# Pour_Over_Board_Internal_Pullup.net
KiCad netlist of a schematic drawn in EAGLE
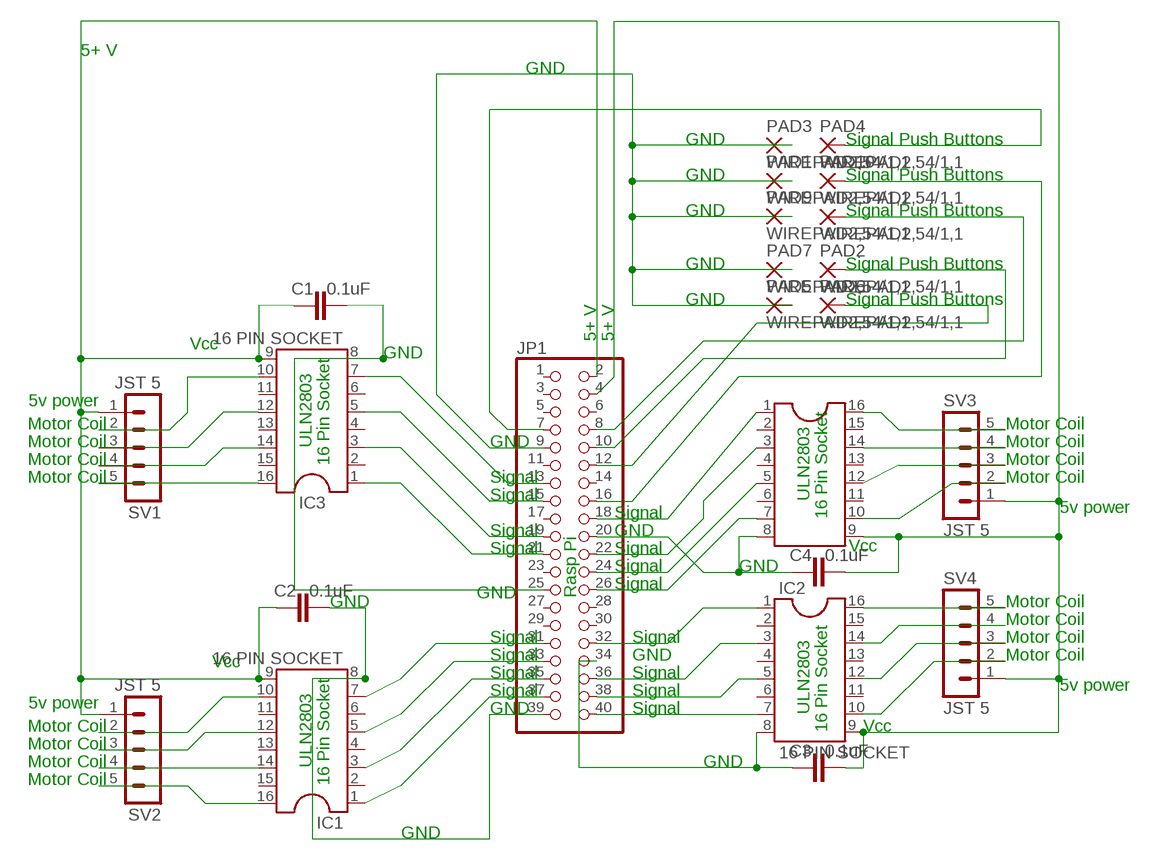
[diagram p0: schematic, sheet 1]

(export (version "E")
  (design (tool "Eeschema 10.0.6"))
  (components
    (comp (ref "C1")
      (value "0.1uF")
      (footprint "eagle-import:CAP-PTH-SMALL-KIT")
      (libsource (lib "eagle-import") (part "0.1UF-KIT-EZ-50V-20%"))
    )
    (comp (ref "C2")
      (value "0.1uF")
      (footprint "eagle-import:CAP-PTH-SMALL-KIT")
      (libsource (lib "eagle-import") (part "0.1UF-KIT-EZ-50V-20%"))
    )
    (comp (ref "C3")
      (value "0.1uF")
      (footprint "eagle-import:CAP-PTH-SMALL-KIT")
      (libsource (lib "eagle-import") (part "0.1UF-KIT-EZ-50V-20%"))
    )
    (comp (ref "C4")
      (value "0.1uF")
      (footprint "eagle-import:CAP-PTH-SMALL-KIT")
      (libsource (lib "eagle-import") (part "0.1UF-KIT-EZ-50V-20%"))
    )
    (comp (ref "IC1")
      (value "16 PIN SOCKET")
      (footprint "eagle-import:SOCKET-16")
      (libsource (lib "eagle-import") (part "DIL16S"))
    )
    (comp (ref "IC2")
      (value "16 PIN SOCKET")
      (footprint "eagle-import:SOCKET-16")
      (libsource (lib "eagle-import") (part "DIL16S"))
    )
    (comp (ref "IC3")
      (value "16 PIN SOCKET")
      (footprint "eagle-import:SOCKET-16")
      (libsource (lib "eagle-import") (part "DIL16S"))
    )
    (comp (ref "IC4")
      (value "16 PIN SOCKET")
      (footprint "eagle-import:SOCKET-16")
      (libsource (lib "eagle-import") (part "DIL16S"))
    )
    (comp (ref "JP1")
      (value "RaspPiZero")
      (footprint "eagle-import:2X20")
      (libsource (lib "eagle-import") (part "PINHD-2X20"))
    )
    (comp (ref "PAD1")
      (value "WIREPAD2,54/1,1")
      (footprint "eagle-import:2,54_1,1")
      (libsource (lib "eagle-import") (part "WIREPAD2,54/1,1"))
    )
    (comp (ref "PAD2")
      (value "WIREPAD2,54/1,1")
      (footprint "eagle-import:2,54_1,1")
      (libsource (lib "eagle-import") (part "WIREPAD2,54/1,1"))
    )
    (comp (ref "PAD3")
      (value "WIREPAD2,54/1,1")
      (footprint "eagle-import:2,54_1,1")
      (libsource (lib "eagle-import") (part "WIREPAD2,54/1,1"))
    )
    (comp (ref "PAD4")
      (value "WIREPAD2,54/1,1")
      (footprint "eagle-import:2,54_1,1")
      (libsource (lib "eagle-import") (part "WIREPAD2,54/1,1"))
    )
    (comp (ref "PAD5")
      (value "WIREPAD2,54/1,1")
      (footprint "eagle-import:2,54_1,1")
      (libsource (lib "eagle-import") (part "WIREPAD2,54/1,1"))
    )
    (comp (ref "PAD6")
      (value "WIREPAD2,54/1,1")
      (footprint "eagle-import:2,54_1,1")
      (libsource (lib "eagle-import") (part "WIREPAD2,54/1,1"))
    )
    (comp (ref "PAD7")
      (value "WIREPAD2,54/1,1")
      (footprint "eagle-import:2,54_1,1")
      (libsource (lib "eagle-import") (part "WIREPAD2,54/1,1"))
    )
    (comp (ref "PAD8")
      (value "WIREPAD2,54/1,1")
      (footprint "eagle-import:2,54_1,1")
      (libsource (lib "eagle-import") (part "WIREPAD2,54/1,1"))
    )
    (comp (ref "PAD9")
      (value "WIREPAD2,54/1,1")
      (footprint "eagle-import:2,54_1,1")
      (libsource (lib "eagle-import") (part "WIREPAD2,54/1,1"))
    )
    (comp (ref "PAD10")
      (value "WIREPAD2,54/1,1")
      (footprint "eagle-import:2,54_1,1")
      (libsource (lib "eagle-import") (part "WIREPAD2,54/1,1"))
    )
    (comp (ref "SV1")
      (value "JST 5")
      (footprint "eagle-import:MA05-1")
      (libsource (lib "eagle-import") (part "MA05-1"))
    )
    (comp (ref "SV2")
      (value "JST 5")
      (footprint "eagle-import:MA05-1")
      (libsource (lib "eagle-import") (part "MA05-1"))
    )
    (comp (ref "SV3")
      (value "JST 5")
      (footprint "eagle-import:MA05-1")
      (libsource (lib "eagle-import") (part "MA05-1"))
    )
    (comp (ref "SV4")
      (value "JST 5")
      (footprint "eagle-import:MA05-1")
      (libsource (lib "eagle-import") (part "MA05-1"))
    )
  )
  (nets
    (net (code "1") (name "Net-(C1-Pad1)") (class "Default")
      (node (ref "C1") (pin "1") (pinfunction "1_1") (pintype "passive"))
      (node (ref "C2") (pin "1") (pinfunction "1_1") (pintype "passive"))
      (node (ref "IC1") (pin "9") (pinfunction "9_9") (pintype "passive"))
      (node (ref "IC3") (pin "9") (pinfunction "9_9") (pintype "passive"))
      (node (ref "JP1") (pin "2") (pinfunction "2_2") (pintype "passive"))
      (node (ref "SV1") (pin "1") (pinfunction "1_1") (pintype "passive"))
      (node (ref "SV2") (pin "1") (pinfunction "1_1") (pintype "passive"))
    )
    (net (code "2") (name "Net-(C1-Pad2)") (class "Default")
      (node (ref "C1") (pin "2") (pinfunction "2_2") (pintype "passive"))
      (node (ref "IC3") (pin "8") (pinfunction "8_8") (pintype "passive"))
      (node (ref "JP1") (pin "25") (pinfunction "25_25") (pintype "passive"))
    )
    (net (code "3") (name "Net-(C2-Pad2)") (class "Default")
      (node (ref "C2") (pin "2") (pinfunction "2_2") (pintype "passive"))
      (node (ref "IC1") (pin "8") (pinfunction "8_8") (pintype "passive"))
      (node (ref "JP1") (pin "39") (pinfunction "39_39") (pintype "passive"))
    )
    (net (code "4") (name "Net-(C3-Pad1)") (class "Default")
      (node (ref "C3") (pin "1") (pinfunction "1_1") (pintype "passive"))
      (node (ref "IC2") (pin "8") (pinfunction "8_8") (pintype "passive"))
      (node (ref "JP1") (pin "34") (pinfunction "34_34") (pintype "passive"))
    )
    (net (code "5") (name "Net-(C3-Pad2)") (class "Default")
      (node (ref "C3") (pin "2") (pinfunction "2_2") (pintype "passive"))
      (node (ref "C4") (pin "2") (pinfunction "2_2") (pintype "passive"))
      (node (ref "IC2") (pin "9") (pinfunction "9_9") (pintype "passive"))
      (node (ref "IC4") (pin "9") (pinfunction "9_9") (pintype "passive"))
      (node (ref "JP1") (pin "4") (pinfunction "4_4") (pintype "passive"))
      (node (ref "SV3") (pin "1") (pinfunction "1_1") (pintype "passive"))
      (node (ref "SV4") (pin "1") (pinfunction "1_1") (pintype "passive"))
    )
    (net (code "6") (name "Net-(C4-Pad1)") (class "Default")
      (node (ref "C4") (pin "1") (pinfunction "1_1") (pintype "passive"))
      (node (ref "IC4") (pin "8") (pinfunction "8_8") (pintype "passive"))
      (node (ref "JP1") (pin "20") (pinfunction "20_20") (pintype "passive"))
    )
    (net (code "7") (name "Net-(IC1-Pad1)") (class "Default")
      (node (ref "IC1") (pin "1") (pinfunction "1_1") (pintype "passive"))
      (node (ref "JP1") (pin "37") (pinfunction "37_37") (pintype "passive"))
    )
    (net (code "8") (name "Net-(IC1-Pad3)") (class "Default")
      (node (ref "IC1") (pin "3") (pinfunction "3_3") (pintype "passive"))
      (node (ref "JP1") (pin "35") (pinfunction "35_35") (pintype "passive"))
    )
    (net (code "9") (name "Net-(IC1-Pad5)") (class "Default")
      (node (ref "IC1") (pin "5") (pinfunction "5_5") (pintype "passive"))
      (node (ref "JP1") (pin "33") (pinfunction "33_33") (pintype "passive"))
    )
    (net (code "10") (name "Net-(IC1-Pad7)") (class "Default")
      (node (ref "IC1") (pin "7") (pinfunction "7_7") (pintype "passive"))
      (node (ref "JP1") (pin "31") (pinfunction "31_31") (pintype "passive"))
    )
    (net (code "11") (name "Net-(IC1-Pad10)") (class "Default")
      (node (ref "IC1") (pin "10") (pinfunction "10_10") (pintype "passive"))
      (node (ref "SV2") (pin "2") (pinfunction "2_2") (pintype "passive"))
    )
    (net (code "12") (name "Net-(IC1-Pad12)") (class "Default")
      (node (ref "IC1") (pin "12") (pinfunction "12_12") (pintype "passive"))
      (node (ref "SV2") (pin "3") (pinfunction "3_3") (pintype "passive"))
    )
    (net (code "13") (name "Net-(IC1-Pad14)") (class "Default")
      (node (ref "IC1") (pin "14") (pinfunction "14_14") (pintype "passive"))
      (node (ref "SV2") (pin "4") (pinfunction "4_4") (pintype "passive"))
    )
    (net (code "14") (name "Net-(IC1-Pad16)") (class "Default")
      (node (ref "IC1") (pin "16") (pinfunction "16_16") (pintype "passive"))
      (node (ref "SV2") (pin "5") (pinfunction "5_5") (pintype "passive"))
    )
    (net (code "15") (name "Net-(IC2-Pad1)") (class "Default")
      (node (ref "IC2") (pin "1") (pinfunction "1_1") (pintype "passive"))
      (node (ref "JP1") (pin "32") (pinfunction "32_32") (pintype "passive"))
    )
    (net (code "16") (name "Net-(IC2-Pad3)") (class "Default")
      (node (ref "IC2") (pin "3") (pinfunction "3_3") (pintype "passive"))
      (node (ref "JP1") (pin "36") (pinfunction "36_36") (pintype "passive"))
    )
    (net (code "17") (name "Net-(IC2-Pad5)") (class "Default")
      (node (ref "IC2") (pin "5") (pinfunction "5_5") (pintype "passive"))
      (node (ref "JP1") (pin "38") (pinfunction "38_38") (pintype "passive"))
    )
    (net (code "18") (name "Net-(IC2-Pad7)") (class "Default")
      (node (ref "IC2") (pin "7") (pinfunction "7_7") (pintype "passive"))
      (node (ref "JP1") (pin "40") (pinfunction "40_40") (pintype "passive"))
    )
    (net (code "19") (name "Net-(IC2-Pad10)") (class "Default")
      (node (ref "IC2") (pin "10") (pinfunction "10_10") (pintype "passive"))
      (node (ref "SV4") (pin "2") (pinfunction "2_2") (pintype "passive"))
    )
    (net (code "20") (name "Net-(IC2-Pad12)") (class "Default")
      (node (ref "IC2") (pin "12") (pinfunction "12_12") (pintype "passive"))
      (node (ref "SV4") (pin "3") (pinfunction "3_3") (pintype "passive"))
    )
    (net (code "21") (name "Net-(IC2-Pad14)") (class "Default")
      (node (ref "IC2") (pin "14") (pinfunction "14_14") (pintype "passive"))
      (node (ref "SV4") (pin "4") (pinfunction "4_4") (pintype "passive"))
    )
    (net (code "22") (name "Net-(IC2-Pad16)") (class "Default")
      (node (ref "IC2") (pin "16") (pinfunction "16_16") (pintype "passive"))
      (node (ref "SV4") (pin "5") (pinfunction "5_5") (pintype "passive"))
    )
    (net (code "23") (name "Net-(IC3-Pad1)") (class "Default")
      (node (ref "IC3") (pin "1") (pinfunction "1_1") (pintype "passive"))
      (node (ref "JP1") (pin "21") (pinfunction "21_21") (pintype "passive"))
    )
    (net (code "24") (name "Net-(IC3-Pad3)") (class "Default")
      (node (ref "IC3") (pin "3") (pinfunction "3_3") (pintype "passive"))
      (node (ref "JP1") (pin "19") (pinfunction "19_19") (pintype "passive"))
    )
    (net (code "25") (name "Net-(IC3-Pad5)") (class "Default")
      (node (ref "IC3") (pin "5") (pinfunction "5_5") (pintype "passive"))
      (node (ref "JP1") (pin "15") (pinfunction "15_15") (pintype "passive"))
    )
    (net (code "26") (name "Net-(IC3-Pad7)") (class "Default")
      (node (ref "IC3") (pin "7") (pinfunction "7_7") (pintype "passive"))
      (node (ref "JP1") (pin "13") (pinfunction "13_13") (pintype "passive"))
    )
    (net (code "27") (name "Net-(IC3-Pad10)") (class "Default")
      (node (ref "IC3") (pin "10") (pinfunction "10_10") (pintype "passive"))
      (node (ref "SV1") (pin "2") (pinfunction "2_2") (pintype "passive"))
    )
    (net (code "28") (name "Net-(IC3-Pad12)") (class "Default")
      (node (ref "IC3") (pin "12") (pinfunction "12_12") (pintype "passive"))
      (node (ref "SV1") (pin "3") (pinfunction "3_3") (pintype "passive"))
    )
    (net (code "29") (name "Net-(IC3-Pad14)") (class "Default")
      (node (ref "IC3") (pin "14") (pinfunction "14_14") (pintype "passive"))
      (node (ref "SV1") (pin "4") (pinfunction "4_4") (pintype "passive"))
    )
    (net (code "30") (name "Net-(IC3-Pad16)") (class "Default")
      (node (ref "IC3") (pin "16") (pinfunction "16_16") (pintype "passive"))
      (node (ref "SV1") (pin "5") (pinfunction "5_5") (pintype "passive"))
    )
    (net (code "31") (name "Net-(IC4-Pad1)") (class "Default")
      (node (ref "IC4") (pin "1") (pinfunction "1_1") (pintype "passive"))
      (node (ref "JP1") (pin "18") (pinfunction "18_18") (pintype "passive"))
    )
    (net (code "32") (name "Net-(IC4-Pad3)") (class "Default")
      (node (ref "IC4") (pin "3") (pinfunction "3_3") (pintype "passive"))
      (node (ref "JP1") (pin "22") (pinfunction "22_22") (pintype "passive"))
    )
    (net (code "33") (name "Net-(IC4-Pad5)") (class "Default")
      (node (ref "IC4") (pin "5") (pinfunction "5_5") (pintype "passive"))
      (node (ref "JP1") (pin "24") (pinfunction "24_24") (pintype "passive"))
    )
    (net (code "34") (name "Net-(IC4-Pad7)") (class "Default")
      (node (ref "IC4") (pin "7") (pinfunction "7_7") (pintype "passive"))
      (node (ref "JP1") (pin "26") (pinfunction "26_26") (pintype "passive"))
    )
    (net (code "35") (name "Net-(IC4-Pad10)") (class "Default")
      (node (ref "IC4") (pin "10") (pinfunction "10_10") (pintype "passive"))
      (node (ref "SV3") (pin "2") (pinfunction "2_2") (pintype "passive"))
    )
    (net (code "36") (name "Net-(IC4-Pad12)") (class "Default")
      (node (ref "IC4") (pin "12") (pinfunction "12_12") (pintype "passive"))
      (node (ref "SV3") (pin "3") (pinfunction "3_3") (pintype "passive"))
    )
    (net (code "37") (name "Net-(IC4-Pad14)") (class "Default")
      (node (ref "IC4") (pin "14") (pinfunction "14_14") (pintype "passive"))
      (node (ref "SV3") (pin "4") (pinfunction "4_4") (pintype "passive"))
    )
    (net (code "38") (name "Net-(IC4-Pad16)") (class "Default")
      (node (ref "IC4") (pin "16") (pinfunction "16_16") (pintype "passive"))
      (node (ref "SV3") (pin "5") (pinfunction "5_5") (pintype "passive"))
    )
    (net (code "39") (name "Net-(PAD1-P)") (class "Default")
      (node (ref "JP1") (pin "9") (pinfunction "9_9") (pintype "passive"))
      (node (ref "PAD1") (pin "1") (pinfunction "P_1") (pintype "passive"))
      (node (ref "PAD3") (pin "1") (pinfunction "P_1") (pintype "passive"))
      (node (ref "PAD5") (pin "1") (pinfunction "P_1") (pintype "passive"))
      (node (ref "PAD7") (pin "1") (pinfunction "P_1") (pintype "passive"))
      (node (ref "PAD9") (pin "1") (pinfunction "P_1") (pintype "passive"))
    )
    (net (code "40") (name "Net-(PAD2-P)") (class "Default")
      (node (ref "JP1") (pin "10") (pinfunction "10_10") (pintype "passive"))
      (node (ref "PAD2") (pin "1") (pinfunction "P_1") (pintype "passive"))
    )
    (net (code "41") (name "Net-(PAD4-P)") (class "Default")
      (node (ref "JP1") (pin "7") (pinfunction "7_7") (pintype "passive"))
      (node (ref "PAD4") (pin "1") (pinfunction "P_1") (pintype "passive"))
    )
    (net (code "42") (name "Net-(PAD6-P)") (class "Default")
      (node (ref "JP1") (pin "12") (pinfunction "12_12") (pintype "passive"))
      (node (ref "PAD6") (pin "1") (pinfunction "P_1") (pintype "passive"))
    )
    (net (code "43") (name "Net-(PAD8-P)") (class "Default")
      (node (ref "JP1") (pin "8") (pinfunction "8_8") (pintype "passive"))
      (node (ref "PAD8") (pin "1") (pinfunction "P_1") (pintype "passive"))
    )
    (net (code "44") (name "Net-(PAD10-P)") (class "Default")
      (node (ref "JP1") (pin "16") (pinfunction "16_16") (pintype "passive"))
      (node (ref "PAD10") (pin "1") (pinfunction "P_1") (pintype "passive"))
    )
    (net (code "45") (name "unconnected-(IC1-Pad2)") (class "Default")
      (node (ref "IC1") (pin "2") (pinfunction "2_2") (pintype "passive"))
    )
    (net (code "46") (name "unconnected-(IC1-Pad4)") (class "Default")
      (node (ref "IC1") (pin "4") (pinfunction "4_4") (pintype "passive"))
    )
    (net (code "47") (name "unconnected-(IC1-Pad6)") (class "Default")
      (node (ref "IC1") (pin "6") (pinfunction "6_6") (pintype "passive"))
    )
    (net (code "48") (name "unconnected-(IC1-Pad11)") (class "Default")
      (node (ref "IC1") (pin "11") (pinfunction "11_11") (pintype "passive"))
    )
    (net (code "49") (name "unconnected-(IC1-Pad13)") (class "Default")
      (node (ref "IC1") (pin "13") (pinfunction "13_13") (pintype "passive"))
    )
    (net (code "50") (name "unconnected-(IC1-Pad15)") (class "Default")
      (node (ref "IC1") (pin "15") (pinfunction "15_15") (pintype "passive"))
    )
    (net (code "51") (name "unconnected-(IC2-Pad2)") (class "Default")
      (node (ref "IC2") (pin "2") (pinfunction "2_2") (pintype "passive"))
    )
    (net (code "52") (name "unconnected-(IC2-Pad4)") (class "Default")
      (node (ref "IC2") (pin "4") (pinfunction "4_4") (pintype "passive"))
    )
    (net (code "53") (name "unconnected-(IC2-Pad6)") (class "Default")
      (node (ref "IC2") (pin "6") (pinfunction "6_6") (pintype "passive"))
    )
    (net (code "54") (name "unconnected-(IC2-Pad11)") (class "Default")
      (node (ref "IC2") (pin "11") (pinfunction "11_11") (pintype "passive"))
    )
    (net (code "55") (name "unconnected-(IC2-Pad13)") (class "Default")
      (node (ref "IC2") (pin "13") (pinfunction "13_13") (pintype "passive"))
    )
    (net (code "56") (name "unconnected-(IC2-Pad15)") (class "Default")
      (node (ref "IC2") (pin "15") (pinfunction "15_15") (pintype "passive"))
    )
    (net (code "57") (name "unconnected-(IC3-Pad2)") (class "Default")
      (node (ref "IC3") (pin "2") (pinfunction "2_2") (pintype "passive"))
    )
    (net (code "58") (name "unconnected-(IC3-Pad4)") (class "Default")
      (node (ref "IC3") (pin "4") (pinfunction "4_4") (pintype "passive"))
    )
    (net (code "59") (name "unconnected-(IC3-Pad6)") (class "Default")
      (node (ref "IC3") (pin "6") (pinfunction "6_6") (pintype "passive"))
    )
    (net (code "60") (name "unconnected-(IC3-Pad11)") (class "Default")
      (node (ref "IC3") (pin "11") (pinfunction "11_11") (pintype "passive"))
    )
    (net (code "61") (name "unconnected-(IC3-Pad13)") (class "Default")
      (node (ref "IC3") (pin "13") (pinfunction "13_13") (pintype "passive"))
    )
    (net (code "62") (name "unconnected-(IC3-Pad15)") (class "Default")
      (node (ref "IC3") (pin "15") (pinfunction "15_15") (pintype "passive"))
    )
    (net (code "63") (name "unconnected-(IC4-Pad2)") (class "Default")
      (node (ref "IC4") (pin "2") (pinfunction "2_2") (pintype "passive"))
    )
    (net (code "64") (name "unconnected-(IC4-Pad4)") (class "Default")
      (node (ref "IC4") (pin "4") (pinfunction "4_4") (pintype "passive"))
    )
    (net (code "65") (name "unconnected-(IC4-Pad6)") (class "Default")
      (node (ref "IC4") (pin "6") (pinfunction "6_6") (pintype "passive"))
    )
    (net (code "66") (name "unconnected-(IC4-Pad11)") (class "Default")
      (node (ref "IC4") (pin "11") (pinfunction "11_11") (pintype "passive"))
    )
    (net (code "67") (name "unconnected-(IC4-Pad13)") (class "Default")
      (node (ref "IC4") (pin "13") (pinfunction "13_13") (pintype "passive"))
    )
    (net (code "68") (name "unconnected-(IC4-Pad15)") (class "Default")
      (node (ref "IC4") (pin "15") (pinfunction "15_15") (pintype "passive"))
    )
    (net (code "69") (name "unconnected-(JP1-Pad1)") (class "Default")
      (node (ref "JP1") (pin "1") (pinfunction "1_1") (pintype "passive"))
    )
    (net (code "70") (name "unconnected-(JP1-Pad3)") (class "Default")
      (node (ref "JP1") (pin "3") (pinfunction "3_3") (pintype "passive"))
    )
    (net (code "71") (name "unconnected-(JP1-Pad5)") (class "Default")
      (node (ref "JP1") (pin "5") (pinfunction "5_5") (pintype "passive"))
    )
    (net (code "72") (name "unconnected-(JP1-Pad6)") (class "Default")
      (node (ref "JP1") (pin "6") (pinfunction "6_6") (pintype "passive"))
    )
    (net (code "73") (name "unconnected-(JP1-Pad11)") (class "Default")
      (node (ref "JP1") (pin "11") (pinfunction "11_11") (pintype "passive"))
    )
    (net (code "74") (name "unconnected-(JP1-Pad14)") (class "Default")
      (node (ref "JP1") (pin "14") (pinfunction "14_14") (pintype "passive"))
    )
    (net (code "75") (name "unconnected-(JP1-Pad17)") (class "Default")
      (node (ref "JP1") (pin "17") (pinfunction "17_17") (pintype "passive"))
    )
    (net (code "76") (name "unconnected-(JP1-Pad23)") (class "Default")
      (node (ref "JP1") (pin "23") (pinfunction "23_23") (pintype "passive"))
    )
    (net (code "77") (name "unconnected-(JP1-Pad27)") (class "Default")
      (node (ref "JP1") (pin "27") (pinfunction "27_27") (pintype "passive"))
    )
    (net (code "78") (name "unconnected-(JP1-Pad28)") (class "Default")
      (node (ref "JP1") (pin "28") (pinfunction "28_28") (pintype "passive"))
    )
    (net (code "79") (name "unconnected-(JP1-Pad29)") (class "Default")
      (node (ref "JP1") (pin "29") (pinfunction "29_29") (pintype "passive"))
    )
    (net (code "80") (name "unconnected-(JP1-Pad30)") (class "Default")
      (node (ref "JP1") (pin "30") (pinfunction "30_30") (pintype "passive"))
    )
  )
)
